# SCH_Celec_Hackathon_j_2025-03-23.net
KiCad netlist of a schematic drawn in EasyEDA
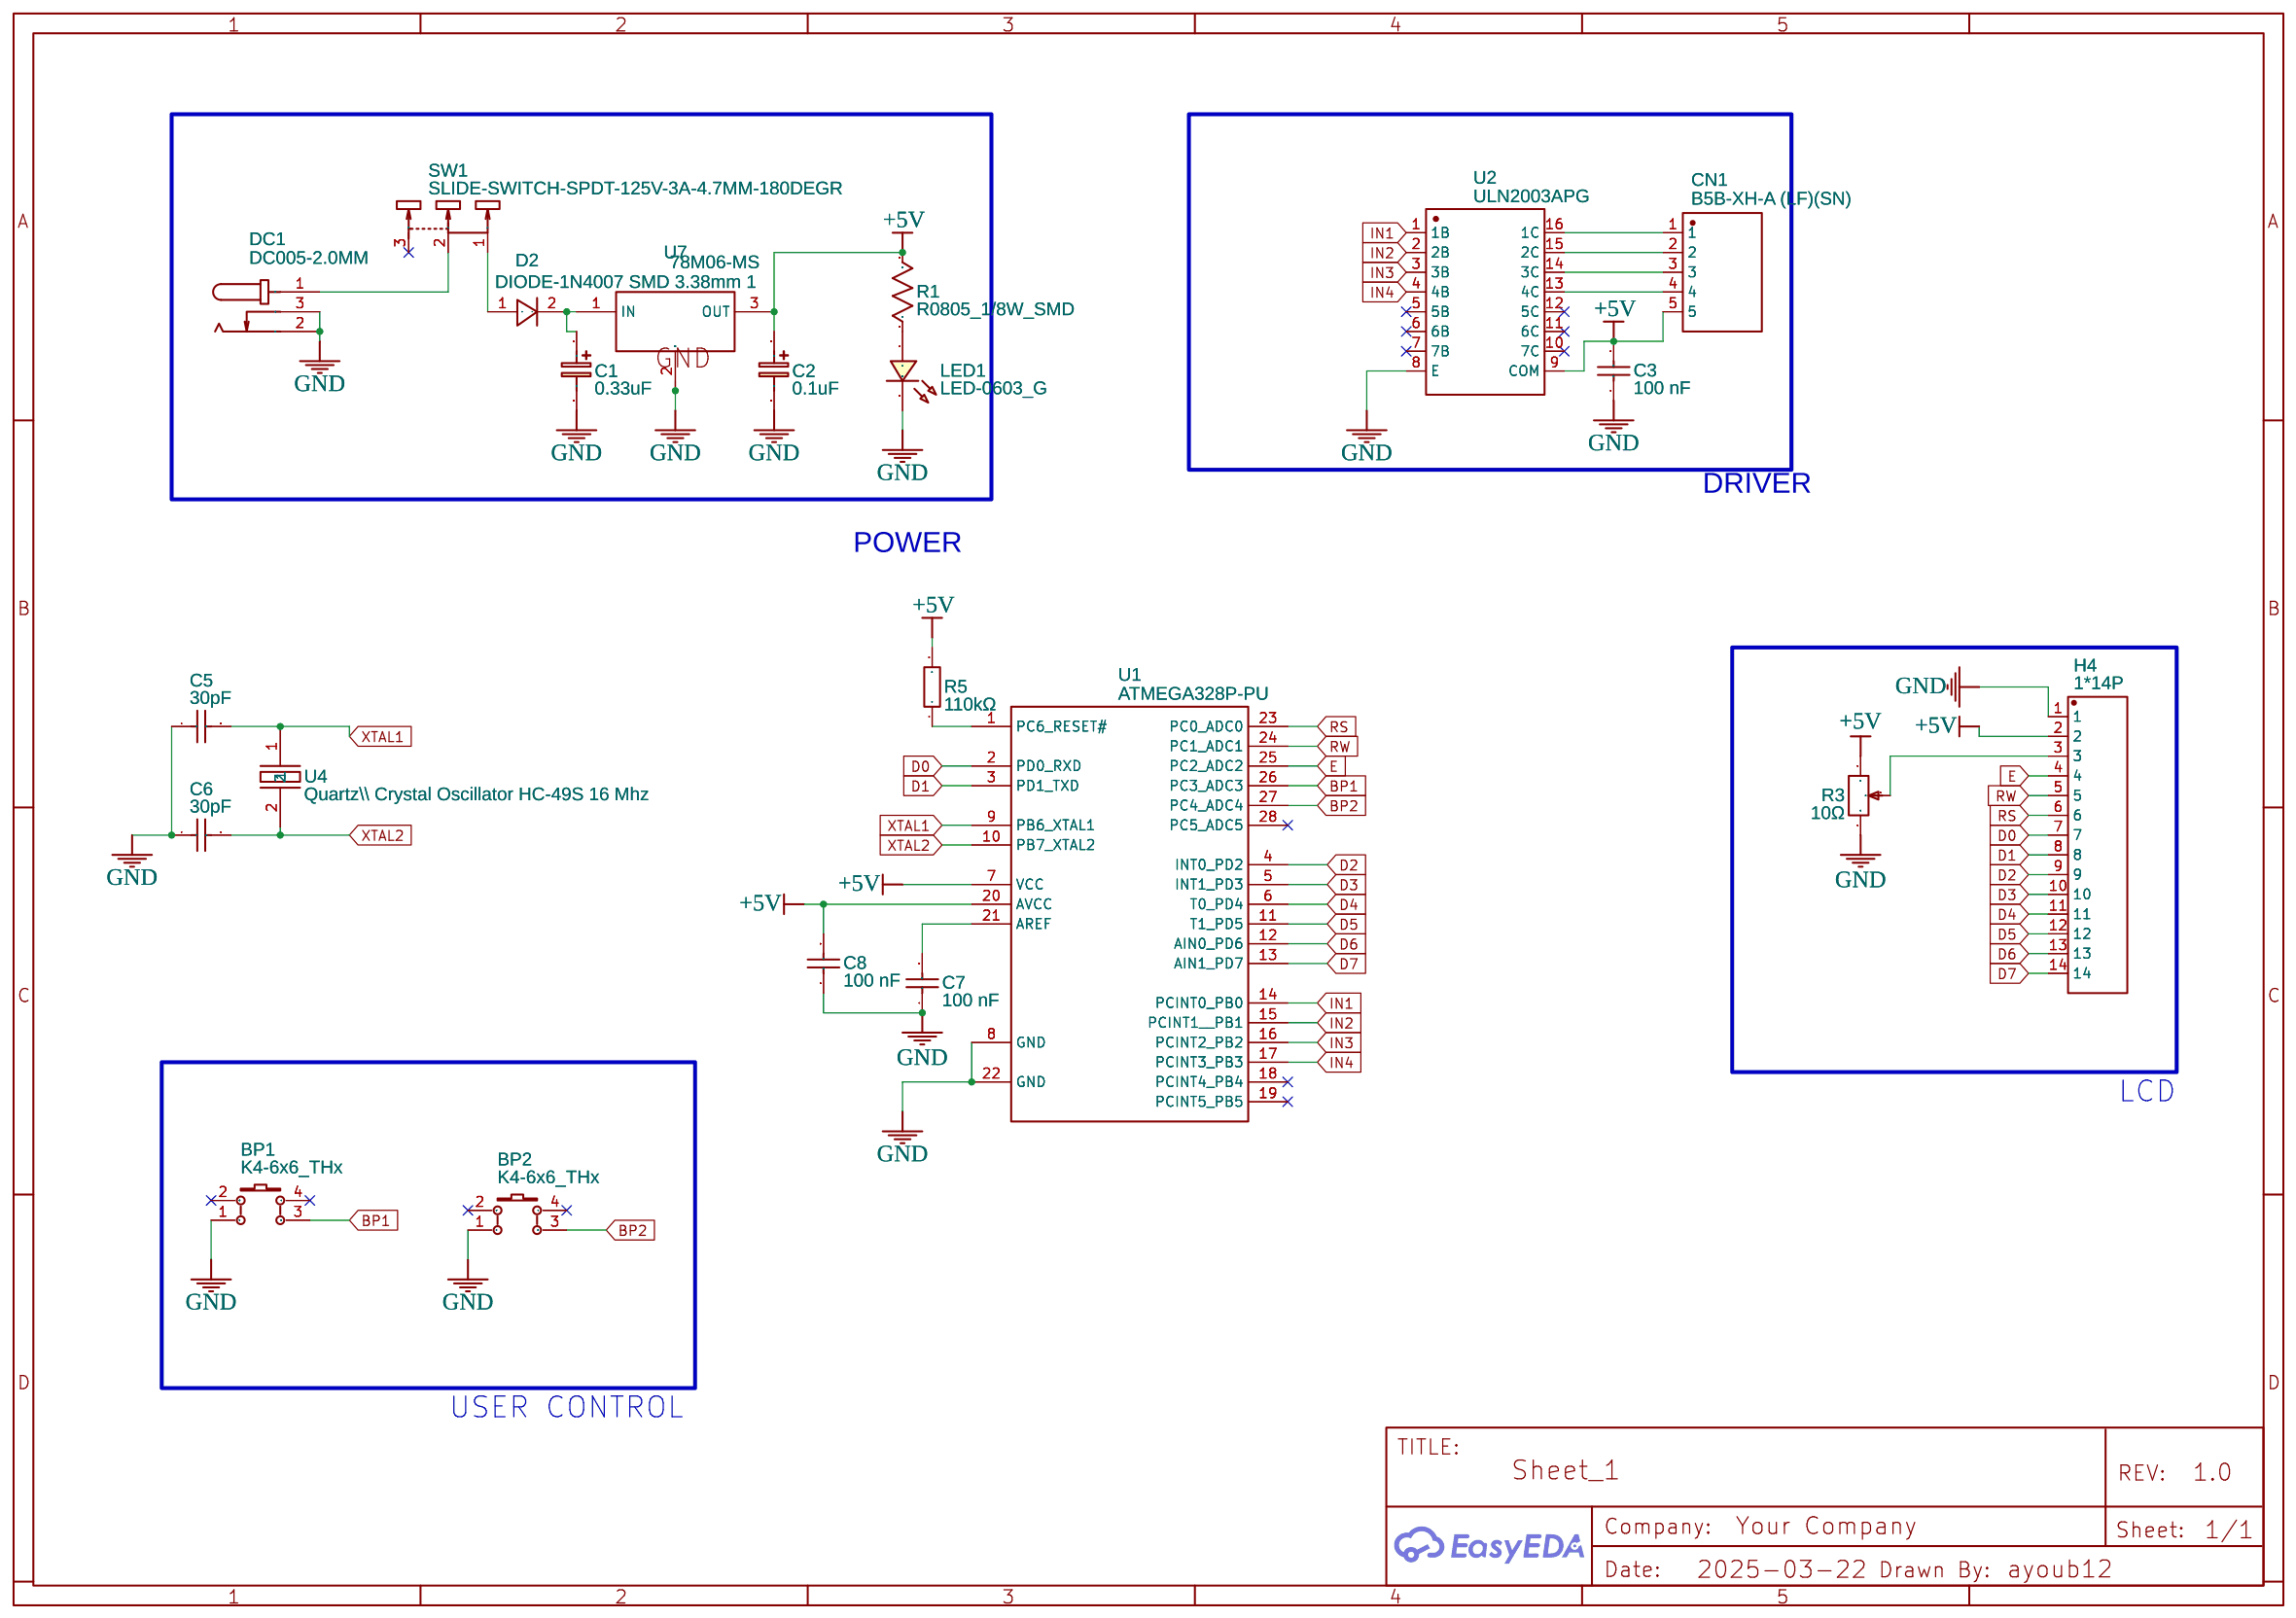
[diagram p0: schematic sheet]

(export (version "E")
  (design (tool "Eeschema 10.0.6"))
  (components
    (comp (ref "BP1") (value "K4-6x6_THx") (libsource (lib "") (part "K4-6x6_THx")))
    (comp (ref "BP2") (value "K4-6x6_THx") (libsource (lib "") (part "K4-6x6_THx")))
    (comp (ref "C1") (value "0.33uF") (libsource (lib "") (part "CE_TH_D3.0×F1.5_EU")))
    (comp (ref "C2") (value "0.1uF") (libsource (lib "") (part "CE_TH_D3.0×F1.5_EU")))
    (comp (ref "C3") (value "100 nF") (libsource (lib "") (part "100 nF")))
    (comp (ref "C5")
      (value "30pF")
      (fields (field (name "Manufacturer Part") "0805CG300J500NT") (field (name "Manufacturer") "FH(风华)"))
      (libsource (lib "") (part "0805CG300J500NT"))
    )
    (comp (ref "C6")
      (value "30pF")
      (fields (field (name "Manufacturer Part") "0805CG300J500NT") (field (name "Manufacturer") "FH(风华)"))
      (libsource (lib "") (part "0805CG300J500NT"))
    )
    (comp (ref "C7") (value "100 nF") (libsource (lib "") (part "100 nF")))
    (comp (ref "C8") (value "100 nF") (libsource (lib "") (part "100 nF")))
    (comp (ref "CN1")
      (value "B5B-XH-A (LF)(SN)")
      (fields (field (name "Manufacturer Part") "B5B-XH-A(LF)(SN)") (field (name "Manufacturer") "JST"))
      (libsource (lib "") (part "B5B-XH-A (LF)(SN)"))
    )
    (comp (ref "D2")
      (value "DIODE-1N4007 SMD 3.38mm 1")
      (libsource (lib "") (part "DIODE-1N4007 SMD 3.38mm 1"))
    )
    (comp (ref "DC1")
      (value "DC005-2.0MM")
      (fields (field (name "Manufacturer") "SOFNG"))
      (libsource (lib "") (part "DC005-2.0MM"))
    )
    (comp (ref "H4")
      (value "1*14P")
      (fields
        (field (name "Manufacturer Part") "210S-1*15P L=11.6MMGold-plated black")
        (field (name "Manufacturer") "Ckmtw")
      )
      (libsource (lib "") (part "1*14P"))
    )
    (comp (ref "LED1")
      (value "LED-0603_G")
      (fields
        (field (name "Manufacturer Part") "19-217/GHC-YR1S2/3T")
        (field (name "Manufacturer") "EVERLIGHT(台湾亿光)")
      )
      (libsource (lib "") (part "LED-0603_G"))
    )
    (comp (ref "R1") (value "R0805_1/8W_SMD") (libsource (lib "") (part "R0805_1/8W_SMD")))
    (comp (ref "R3")
      (value "10Ω")
      (fields (field (name "Manufacturer Part") "3362P-1-100LF") (field (name "Manufacturer") "BOURNS"))
      (libsource (lib "") (part "3362P-1-100LF"))
    )
    (comp (ref "R5")
      (value "110kΩ")
      (fields
        (field (name "Manufacturer Part") "CF1/4W-110KΩ±5% T52")
        (field (name "Manufacturer") "CCO(千志电子)")
      )
      (libsource (lib "") (part "CF1/4W-110KΩ±5% T52"))
    )
    (comp (ref "SW1")
      (value "SLIDE-SWITCH-SPDT-125V-3A-4.7MM-180DEGR")
      (fields
        (field (name "Manufacturer Part") "SS-12D10L3")
        (field (name "Manufacturer") "XKB Connectivity(中国星坤)")
      )
      (libsource (lib "") (part "SLIDE-SWITCH-SPDT-125V-3A-4.7MM-180DEGR"))
    )
    (comp (ref "U1")
      (value "ATMEGA328P-PU")
      (fields (field (name "Manufacturer") "MICROCHIP(美国微芯)"))
      (libsource (lib "") (part "ATMEGA328P-PU"))
    )
    (comp (ref "U2")
      (value "ULN2003APG")
      (fields (field (name "Manufacturer") "TOSHIBA(东芝)"))
      (libsource (lib "") (part "ULN2003APG"))
    )
    (comp (ref "U4")
      (value "Quartz\\\\ Crystal Oscillator HC-49S 16 Mhz")
      (libsource (lib "") (part "Quartz{backslash}{backslash} Crystal Oscillator HC-49S 16 Mhz"))
    )
    (comp (ref "U7")
      (value "78M06-MS")
      (fields (field (name "Manufacturer") "MSKSEMI(美森科)"))
      (libsource (lib "") (part "78M06-MS"))
    )
  )
  (nets
    (net (code "1") (name "+5V") (class "Default")
      (node (ref "C2") (pin "1") (pinfunction "1_1") (pintype "unspecified"))
      (node (ref "C3") (pin "2") (pinfunction "2_2") (pintype "input"))
      (node (ref "C8") (pin "2") (pinfunction "2_2") (pintype "input"))
      (node (ref "CN1") (pin "5") (pinfunction "5_5") (pintype "unspecified"))
      (node (ref "H4") (pin "2") (pinfunction "2_2") (pintype "unspecified"))
      (node (ref "R1") (pin "2") (pinfunction "2_2") (pintype "unspecified"))
      (node (ref "R3") (pin "1") (pinfunction "1_1") (pintype "input"))
      (node (ref "R5") (pin "2") (pinfunction "2_2") (pintype "unspecified"))
      (node (ref "U1") (pin "20") (pinfunction "AVCC_20") (pintype "passive"))
      (node (ref "U1") (pin "7") (pinfunction "VCC_7") (pintype "passive"))
      (node (ref "U2") (pin "9") (pinfunction "COM_9") (pintype "unspecified"))
      (node (ref "U7") (pin "3") (pinfunction "OUT_3") (pintype "passive"))
    )
    (net (code "2") (name "BP1") (class "Default")
      (node (ref "BP1") (pin "3") (pinfunction "3_3") (pintype "unspecified"))
      (node (ref "U1") (pin "26") (pinfunction "PC3_ADC3_26") (pintype "bidirectional"))
    )
    (net (code "3") (name "BP2") (class "Default")
      (node (ref "BP2") (pin "3") (pinfunction "3_3") (pintype "unspecified"))
      (node (ref "U1") (pin "27") (pinfunction "PC4_ADC4_27") (pintype "bidirectional"))
    )
    (net (code "4") (name "D0") (class "Default")
      (node (ref "H4") (pin "7") (pinfunction "7_7") (pintype "unspecified"))
      (node (ref "U1") (pin "2") (pinfunction "PD0_RXD_2") (pintype "bidirectional"))
    )
    (net (code "5") (name "D1") (class "Default")
      (node (ref "H4") (pin "8") (pinfunction "8_8") (pintype "unspecified"))
      (node (ref "U1") (pin "3") (pinfunction "PD1_TXD_3") (pintype "bidirectional"))
    )
    (net (code "6") (name "D2") (class "Default")
      (node (ref "H4") (pin "9") (pinfunction "9_9") (pintype "unspecified"))
      (node (ref "U1") (pin "4") (pinfunction "INT0_PD2_4") (pintype "bidirectional"))
    )
    (net (code "7") (name "D3") (class "Default")
      (node (ref "H4") (pin "10") (pinfunction "10_10") (pintype "unspecified"))
      (node (ref "U1") (pin "5") (pinfunction "INT1_PD3_5") (pintype "bidirectional"))
    )
    (net (code "8") (name "D4") (class "Default")
      (node (ref "H4") (pin "11") (pinfunction "11_11") (pintype "unspecified"))
      (node (ref "U1") (pin "6") (pinfunction "T0_PD4_6") (pintype "bidirectional"))
    )
    (net (code "9") (name "D5") (class "Default")
      (node (ref "H4") (pin "12") (pinfunction "12_12") (pintype "unspecified"))
      (node (ref "U1") (pin "11") (pinfunction "T1_PD5_11") (pintype "bidirectional"))
    )
    (net (code "10") (name "D6") (class "Default")
      (node (ref "H4") (pin "13") (pinfunction "13_13") (pintype "unspecified"))
      (node (ref "U1") (pin "12") (pinfunction "AIN0_PD6_12") (pintype "bidirectional"))
    )
    (net (code "11") (name "D7") (class "Default")
      (node (ref "H4") (pin "14") (pinfunction "14_14") (pintype "unspecified"))
      (node (ref "U1") (pin "13") (pinfunction "AIN1_PD7_13") (pintype "bidirectional"))
    )
    (net (code "12") (name "E") (class "Default")
      (node (ref "H4") (pin "4") (pinfunction "4_4") (pintype "unspecified"))
      (node (ref "U1") (pin "25") (pinfunction "PC2_ADC2_25") (pintype "bidirectional"))
    )
    (net (code "13") (name "GND") (class "Default")
      (node (ref "BP1") (pin "1") (pinfunction "1_1") (pintype "unspecified"))
      (node (ref "BP2") (pin "1") (pinfunction "1_1") (pintype "unspecified"))
      (node (ref "C1") (pin "2") (pinfunction "2_2") (pintype "unspecified"))
      (node (ref "C2") (pin "2") (pinfunction "2_2") (pintype "unspecified"))
      (node (ref "C3") (pin "1") (pinfunction "1_1") (pintype "input"))
      (node (ref "C5") (pin "1") (pinfunction "1_1") (pintype "input"))
      (node (ref "C6") (pin "1") (pinfunction "1_1") (pintype "input"))
      (node (ref "C7") (pin "1") (pinfunction "1_1") (pintype "input"))
      (node (ref "C8") (pin "1") (pinfunction "1_1") (pintype "input"))
      (node (ref "DC1") (pin "2") (pinfunction "2_2") (pintype "unspecified"))
      (node (ref "DC1") (pin "3") (pinfunction "3_3") (pintype "unspecified"))
      (node (ref "H4") (pin "1") (pinfunction "1_1") (pintype "unspecified"))
      (node (ref "LED1") (pin "2") (pinfunction "2_2") (pintype "unspecified"))
      (node (ref "R3") (pin "3") (pinfunction "3_3") (pintype "input"))
      (node (ref "U1") (pin "22") (pinfunction "GND_22") (pintype "passive"))
      (node (ref "U1") (pin "8") (pinfunction "GND_8") (pintype "passive"))
      (node (ref "U2") (pin "8") (pinfunction "E_8") (pintype "unspecified"))
      (node (ref "U7") (pin "2") (pinfunction "GND_2") (pintype "passive"))
    )
    (net (code "14") (name "IN1") (class "Default")
      (node (ref "U1") (pin "14") (pinfunction "PCINT0_PB0_14") (pintype "bidirectional"))
      (node (ref "U2") (pin "1") (pinfunction "1B_1") (pintype "unspecified"))
    )
    (net (code "15") (name "IN2") (class "Default")
      (node (ref "U1") (pin "15") (pinfunction "PCINT1__PB1_15") (pintype "bidirectional"))
      (node (ref "U2") (pin "2") (pinfunction "2B_2") (pintype "unspecified"))
    )
    (net (code "16") (name "IN3") (class "Default")
      (node (ref "U1") (pin "16") (pinfunction "PCINT2_PB2_16") (pintype "bidirectional"))
      (node (ref "U2") (pin "3") (pinfunction "3B_3") (pintype "unspecified"))
    )
    (net (code "17") (name "IN4") (class "Default")
      (node (ref "U1") (pin "17") (pinfunction "PCINT3_PB3_17") (pintype "bidirectional"))
      (node (ref "U2") (pin "4") (pinfunction "4B_4") (pintype "unspecified"))
    )
    (net (code "18") (name "Net-(D2-+)") (class "Default")
      (node (ref "D2") (pin "1") (pinfunction "+_1") (pintype "unspecified"))
      (node (ref "SW1") (pin "1") (pinfunction "1_1") (pintype "unspecified"))
    )
    (net (code "19") (name "Net-(D2--)") (class "Default")
      (node (ref "C1") (pin "1") (pinfunction "1_1") (pintype "unspecified"))
      (node (ref "D2") (pin "2") (pinfunction "-_2") (pintype "unspecified"))
      (node (ref "U7") (pin "1") (pinfunction "IN_1") (pintype "passive"))
    )
    (net (code "20") (name "Net-(DC1-Pad1)") (class "Default")
      (node (ref "DC1") (pin "1") (pinfunction "1_1") (pintype "unspecified"))
      (node (ref "SW1") (pin "2") (pinfunction "2_2") (pintype "unspecified"))
    )
    (net (code "21") (name "Net-(H4-Pad3)") (class "Default")
      (node (ref "H4") (pin "3") (pinfunction "3_3") (pintype "unspecified"))
      (node (ref "R3") (pin "2") (pinfunction "2_2") (pintype "input"))
    )
    (net (code "22") (name "Net-(LED1-Pad1)") (class "Default")
      (node (ref "LED1") (pin "1") (pinfunction "1_1") (pintype "unspecified"))
      (node (ref "R1") (pin "1") (pinfunction "1_1") (pintype "unspecified"))
    )
    (net (code "23") (name "Net-(U1-AREF)") (class "Default")
      (node (ref "C7") (pin "2") (pinfunction "2_2") (pintype "input"))
      (node (ref "U1") (pin "21") (pinfunction "AREF_21") (pintype "passive"))
    )
    (net (code "24") (name "Net-(U1-PC6_RESET#)") (class "Default")
      (node (ref "R5") (pin "1") (pinfunction "1_1") (pintype "unspecified"))
      (node (ref "U1") (pin "1") (pinfunction "PC6_RESET#_1") (pintype "bidirectional"))
    )
    (net (code "25") (name "Net-(U2-1C)") (class "Default")
      (node (ref "CN1") (pin "1") (pinfunction "1_1") (pintype "unspecified"))
      (node (ref "U2") (pin "16") (pinfunction "1C_16") (pintype "unspecified"))
    )
    (net (code "26") (name "Net-(U2-2C)") (class "Default")
      (node (ref "CN1") (pin "2") (pinfunction "2_2") (pintype "unspecified"))
      (node (ref "U2") (pin "15") (pinfunction "2C_15") (pintype "unspecified"))
    )
    (net (code "27") (name "Net-(U2-3C)") (class "Default")
      (node (ref "CN1") (pin "3") (pinfunction "3_3") (pintype "unspecified"))
      (node (ref "U2") (pin "14") (pinfunction "3C_14") (pintype "unspecified"))
    )
    (net (code "28") (name "Net-(U2-4C)") (class "Default")
      (node (ref "CN1") (pin "4") (pinfunction "4_4") (pintype "unspecified"))
      (node (ref "U2") (pin "13") (pinfunction "4C_13") (pintype "unspecified"))
    )
    (net (code "29") (name "RS") (class "Default")
      (node (ref "H4") (pin "6") (pinfunction "6_6") (pintype "unspecified"))
      (node (ref "U1") (pin "23") (pinfunction "PC0_ADC0_23") (pintype "bidirectional"))
    )
    (net (code "30") (name "RW") (class "Default")
      (node (ref "H4") (pin "5") (pinfunction "5_5") (pintype "unspecified"))
      (node (ref "U1") (pin "24") (pinfunction "PC1_ADC1_24") (pintype "bidirectional"))
    )
    (net (code "31") (name "XTAL1") (class "Default")
      (node (ref "C5") (pin "2") (pinfunction "2_2") (pintype "input"))
      (node (ref "U1") (pin "9") (pinfunction "PB6_XTAL1_9") (pintype "bidirectional"))
      (node (ref "U4") (pin "1") (pinfunction "1_1") (pintype "unspecified"))
    )
    (net (code "32") (name "XTAL2") (class "Default")
      (node (ref "C6") (pin "2") (pinfunction "2_2") (pintype "input"))
      (node (ref "U1") (pin "10") (pinfunction "PB7_XTAL2_10") (pintype "bidirectional"))
      (node (ref "U4") (pin "2") (pinfunction "2_2") (pintype "unspecified"))
    )
    (net (code "33") (name "unconnected-(BP1-Pad2)") (class "Default")
      (node (ref "BP1") (pin "2") (pinfunction "2_2") (pintype "unspecified+no_connect"))
    )
    (net (code "34") (name "unconnected-(BP1-Pad4)") (class "Default")
      (node (ref "BP1") (pin "4") (pinfunction "4_4") (pintype "unspecified+no_connect"))
    )
    (net (code "35") (name "unconnected-(BP2-Pad2)") (class "Default")
      (node (ref "BP2") (pin "2") (pinfunction "2_2") (pintype "unspecified+no_connect"))
    )
    (net (code "36") (name "unconnected-(BP2-Pad4)") (class "Default")
      (node (ref "BP2") (pin "4") (pinfunction "4_4") (pintype "unspecified+no_connect"))
    )
    (net (code "37") (name "unconnected-(SW1-Pad3)") (class "Default")
      (node (ref "SW1") (pin "3") (pinfunction "3_3") (pintype "unspecified+no_connect"))
    )
    (net (code "38") (name "unconnected-(U1-PC5_ADC5-Pad28)") (class "Default")
      (node (ref "U1") (pin "28") (pinfunction "PC5_ADC5_28") (pintype "bidirectional+no_connect"))
    )
    (net (code "39") (name "unconnected-(U1-PCINT4_PB4-Pad18)") (class "Default")
      (node (ref "U1") (pin "18") (pinfunction "PCINT4_PB4_18") (pintype "bidirectional+no_connect"))
    )
    (net (code "40") (name "unconnected-(U1-PCINT5_PB5-Pad19)") (class "Default")
      (node (ref "U1") (pin "19") (pinfunction "PCINT5_PB5_19") (pintype "bidirectional+no_connect"))
    )
    (net (code "41") (name "unconnected-(U2-5B-Pad5)") (class "Default")
      (node (ref "U2") (pin "5") (pinfunction "5B_5") (pintype "unspecified+no_connect"))
    )
    (net (code "42") (name "unconnected-(U2-5C-Pad12)") (class "Default")
      (node (ref "U2") (pin "12") (pinfunction "5C_12") (pintype "unspecified+no_connect"))
    )
    (net (code "43") (name "unconnected-(U2-6B-Pad6)") (class "Default")
      (node (ref "U2") (pin "6") (pinfunction "6B_6") (pintype "unspecified+no_connect"))
    )
    (net (code "44") (name "unconnected-(U2-6C-Pad11)") (class "Default")
      (node (ref "U2") (pin "11") (pinfunction "6C_11") (pintype "unspecified+no_connect"))
    )
    (net (code "45") (name "unconnected-(U2-7B-Pad7)") (class "Default")
      (node (ref "U2") (pin "7") (pinfunction "7B_7") (pintype "unspecified+no_connect"))
    )
    (net (code "46") (name "unconnected-(U2-7C-Pad10)") (class "Default")
      (node (ref "U2") (pin "10") (pinfunction "7C_10") (pintype "unspecified+no_connect"))
    )
  )
)
